# 2403_RAM.net
KiCad netlist of a schematic drawn in Altium Designer
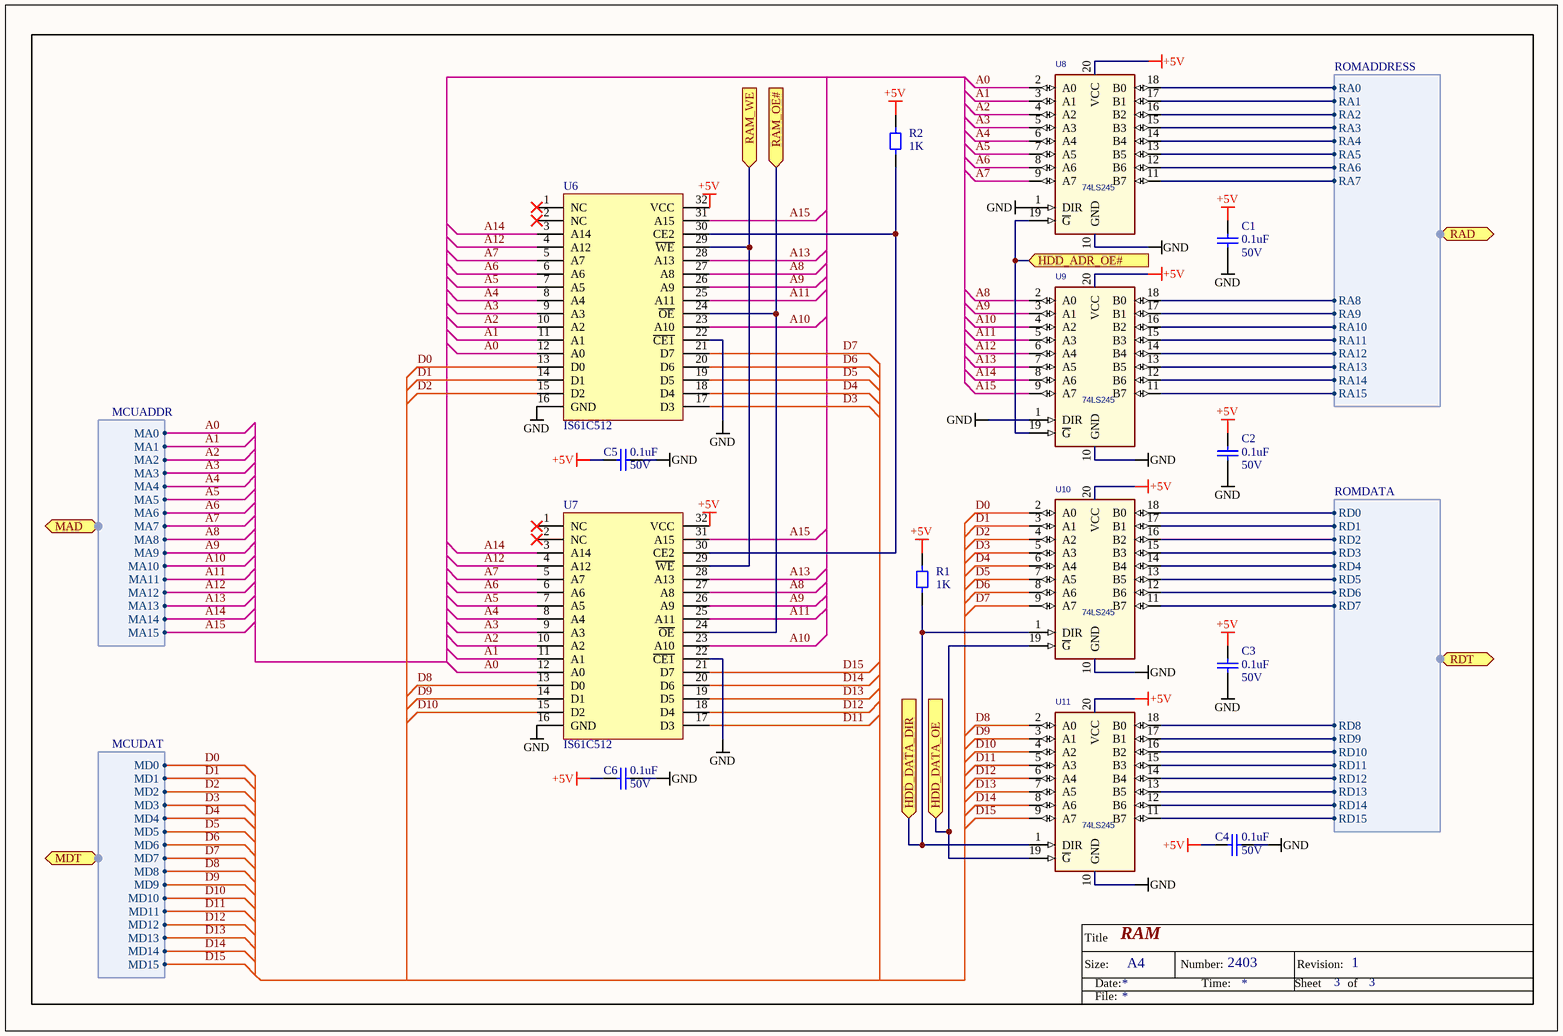
[diagram p0: 2403_RAM.SchDoc]

(export (version "E")
  (design (tool "Eeschema 10.0.6"))
  (components
    (comp (ref "C1")
      (value "0.1uF")
      (footprint "0805_CAPC2013X100N")
      (description "Capacitor SMD")
      (fields (field (name "RATED VOLTAGE") "50V") (field (name "PUBLISHER") "SY"))
      (libsource (lib "Prj24_Library") (part "Cap SMD"))
    )
    (comp (ref "C2")
      (value "0.1uF")
      (footprint "0805_CAPC2013X100N")
      (description "Capacitor SMD")
      (fields (field (name "RATED VOLTAGE") "50V") (field (name "PUBLISHER") "SY"))
      (libsource (lib "Prj24_Library") (part "Cap SMD"))
    )
    (comp (ref "C3")
      (value "0.1uF")
      (footprint "0805_CAPC2013X100N")
      (description "Capacitor SMD")
      (fields (field (name "RATED VOLTAGE") "50V") (field (name "PUBLISHER") "SY"))
      (libsource (lib "Prj24_Library") (part "Cap SMD"))
    )
    (comp (ref "C4")
      (value "0.1uF")
      (footprint "0805_CAPC2013X100N")
      (description "Capacitor SMD")
      (fields (field (name "RATED VOLTAGE") "50V") (field (name "PUBLISHER") "SY"))
      (libsource (lib "Prj24_Library") (part "Cap SMD"))
    )
    (comp (ref "C5")
      (value "0.1uF")
      (footprint "0805_CAPC2013X100N")
      (description "Capacitor SMD")
      (fields (field (name "RATED VOLTAGE") "50V") (field (name "PUBLISHER") "SY"))
      (libsource (lib "Prj24_Library") (part "Cap SMD"))
    )
    (comp (ref "C6")
      (value "0.1uF")
      (footprint "0805_CAPC2013X100N")
      (description "Capacitor SMD")
      (fields (field (name "RATED VOLTAGE") "50V") (field (name "PUBLISHER") "SY"))
      (libsource (lib "Prj24_Library") (part "Cap SMD"))
    )
    (comp (ref "R1")
      (value "1K")
      (footprint "0805_RESC2013X84N")
      (description "SMD Resistor")
      (fields (field (name "TOLERANCE") "5%") (field (name "POWER") "0.1W") (field (name "PUBLISHER") "SY"))
      (libsource (lib "Prj24_Library") (part "Resistor SMD L"))
    )
    (comp (ref "R2")
      (value "1K")
      (footprint "0805_RESC2013X84N")
      (description "SMD Resistor")
      (fields (field (name "TOLERANCE") "5%") (field (name "POWER") "0.1W") (field (name "PUBLISHER") "SY"))
      (libsource (lib "Prj24_Library") (part "Resistor SMD L"))
    )
    (comp (ref "U6")
      (value "IS61C512")
      (footprint "DIP32-300")
      (description "64KB static RAM")
      (fields (field (name "PUBLISHER") "SY"))
      (libsource (lib "Prj24_Library") (part "IS61C512"))
    )
    (comp (ref "U7")
      (value "IS61C512")
      (footprint "DIP32-300")
      (description "64KB static RAM")
      (fields (field (name "PUBLISHER") "SY"))
      (libsource (lib "Prj24_Library") (part "IS61C512"))
    )
    (comp (ref "U8")
      (value "74LS245")
      (footprint "SOIC127P1030X265-20N")
      (description "Bus former")
      (fields (field (name "PUBLISHER") "SY"))
      (libsource (lib "Prj24_Library") (part "74ABT245"))
    )
    (comp (ref "U9")
      (value "74LS245")
      (footprint "SOIC127P1030X265-20N")
      (description "Bus former")
      (fields (field (name "PUBLISHER") "SY"))
      (libsource (lib "Prj24_Library") (part "74ABT245"))
    )
    (comp (ref "U10")
      (value "74LS245")
      (footprint "SOIC127P1030X265-20N")
      (description "Bus former")
      (fields (field (name "PUBLISHER") "SY"))
      (libsource (lib "Prj24_Library") (part "74ABT245"))
    )
    (comp (ref "U11")
      (value "74LS245")
      (footprint "SOIC127P1030X265-20N")
      (description "Bus former")
      (fields (field (name "PUBLISHER") "SY"))
      (libsource (lib "Prj24_Library") (part "74ABT245"))
    )
  )
  (nets
    (net (code "5") (name "+5V") (class "Default")
      (node (ref "C1") (pin "2") (pinfunction "2_2") (pintype "passive"))
      (node (ref "C2") (pin "2") (pinfunction "2_2") (pintype "passive"))
      (node (ref "C3") (pin "2") (pinfunction "2_2") (pintype "passive"))
      (node (ref "C4") (pin "2") (pinfunction "2_2") (pintype "passive"))
      (node (ref "C5") (pin "2") (pinfunction "2_2") (pintype "passive"))
      (node (ref "C6") (pin "2") (pinfunction "2_2") (pintype "passive"))
      (node (ref "R1") (pin "2") (pinfunction "2_2") (pintype "passive"))
      (node (ref "R2") (pin "2") (pinfunction "2_2") (pintype "passive"))
      (node (ref "U10") (pin "20") (pinfunction "VCC_20") (pintype "power_in"))
      (node (ref "U11") (pin "20") (pinfunction "VCC_20") (pintype "power_in"))
      (node (ref "U6") (pin "32") (pinfunction "VCC_32") (pintype "passive"))
      (node (ref "U7") (pin "32") (pinfunction "VCC_32") (pintype "passive"))
      (node (ref "U8") (pin "20") (pinfunction "VCC_20") (pintype "power_in"))
      (node (ref "U9") (pin "20") (pinfunction "VCC_20") (pintype "power_in"))
    )
    (net (code "6") (name "/A0") (class "Default")
      (node (ref "U6") (pin "12") (pinfunction "A0_12") (pintype "passive"))
      (node (ref "U7") (pin "12") (pinfunction "A0_12") (pintype "passive"))
      (node (ref "U8") (pin "2") (pinfunction "A0_2") (pintype "bidirectional"))
    )
    (net (code "7") (name "/A1") (class "Default")
      (node (ref "U6") (pin "11") (pinfunction "A1_11") (pintype "passive"))
      (node (ref "U7") (pin "11") (pinfunction "A1_11") (pintype "passive"))
      (node (ref "U8") (pin "3") (pinfunction "A1_3") (pintype "bidirectional"))
    )
    (net (code "8") (name "/A2") (class "Default")
      (node (ref "U6") (pin "10") (pinfunction "A2_10") (pintype "passive"))
      (node (ref "U7") (pin "10") (pinfunction "A2_10") (pintype "passive"))
      (node (ref "U8") (pin "4") (pinfunction "A2_4") (pintype "bidirectional"))
    )
    (net (code "9") (name "/A3") (class "Default")
      (node (ref "U6") (pin "9") (pinfunction "A3_9") (pintype "passive"))
      (node (ref "U7") (pin "9") (pinfunction "A3_9") (pintype "passive"))
      (node (ref "U8") (pin "5") (pinfunction "A3_5") (pintype "bidirectional"))
    )
    (net (code "10") (name "/A4") (class "Default")
      (node (ref "U6") (pin "8") (pinfunction "A4_8") (pintype "passive"))
      (node (ref "U7") (pin "8") (pinfunction "A4_8") (pintype "passive"))
      (node (ref "U8") (pin "6") (pinfunction "A4_6") (pintype "bidirectional"))
    )
    (net (code "11") (name "/A5") (class "Default")
      (node (ref "U6") (pin "7") (pinfunction "A5_7") (pintype "passive"))
      (node (ref "U7") (pin "7") (pinfunction "A5_7") (pintype "passive"))
      (node (ref "U8") (pin "7") (pinfunction "A5_7") (pintype "bidirectional"))
    )
    (net (code "12") (name "/A6") (class "Default")
      (node (ref "U6") (pin "6") (pinfunction "A6_6") (pintype "passive"))
      (node (ref "U7") (pin "6") (pinfunction "A6_6") (pintype "passive"))
      (node (ref "U8") (pin "8") (pinfunction "A6_8") (pintype "bidirectional"))
    )
    (net (code "13") (name "/A7") (class "Default")
      (node (ref "U6") (pin "5") (pinfunction "A7_5") (pintype "passive"))
      (node (ref "U7") (pin "5") (pinfunction "A7_5") (pintype "passive"))
      (node (ref "U8") (pin "9") (pinfunction "A7_9") (pintype "bidirectional"))
    )
    (net (code "14") (name "/A8") (class "Default")
      (node (ref "U6") (pin "27") (pinfunction "A8_27") (pintype "passive"))
      (node (ref "U7") (pin "27") (pinfunction "A8_27") (pintype "passive"))
      (node (ref "U9") (pin "2") (pinfunction "A0_2") (pintype "bidirectional"))
    )
    (net (code "15") (name "/A9") (class "Default")
      (node (ref "U6") (pin "26") (pinfunction "A9_26") (pintype "passive"))
      (node (ref "U7") (pin "26") (pinfunction "A9_26") (pintype "passive"))
      (node (ref "U9") (pin "3") (pinfunction "A1_3") (pintype "bidirectional"))
    )
    (net (code "16") (name "/A10") (class "Default")
      (node (ref "U6") (pin "23") (pinfunction "A10_23") (pintype "passive"))
      (node (ref "U7") (pin "23") (pinfunction "A10_23") (pintype "passive"))
      (node (ref "U9") (pin "4") (pinfunction "A2_4") (pintype "bidirectional"))
    )
    (net (code "17") (name "/A11") (class "Default")
      (node (ref "U6") (pin "25") (pinfunction "A11_25") (pintype "passive"))
      (node (ref "U7") (pin "25") (pinfunction "A11_25") (pintype "passive"))
      (node (ref "U9") (pin "5") (pinfunction "A3_5") (pintype "bidirectional"))
    )
    (net (code "18") (name "/A12") (class "Default")
      (node (ref "U6") (pin "4") (pinfunction "A12_4") (pintype "passive"))
      (node (ref "U7") (pin "4") (pinfunction "A12_4") (pintype "passive"))
      (node (ref "U9") (pin "6") (pinfunction "A4_6") (pintype "bidirectional"))
    )
    (net (code "19") (name "/A13") (class "Default")
      (node (ref "U6") (pin "28") (pinfunction "A13_28") (pintype "passive"))
      (node (ref "U7") (pin "28") (pinfunction "A13_28") (pintype "passive"))
      (node (ref "U9") (pin "7") (pinfunction "A5_7") (pintype "bidirectional"))
    )
    (net (code "20") (name "/A14") (class "Default")
      (node (ref "U6") (pin "3") (pinfunction "A14_3") (pintype "passive"))
      (node (ref "U7") (pin "3") (pinfunction "A14_3") (pintype "passive"))
      (node (ref "U9") (pin "8") (pinfunction "A6_8") (pintype "bidirectional"))
    )
    (net (code "21") (name "/A15") (class "Default")
      (node (ref "U6") (pin "31") (pinfunction "A15_31") (pintype "passive"))
      (node (ref "U7") (pin "31") (pinfunction "A15_31") (pintype "passive"))
      (node (ref "U9") (pin "9") (pinfunction "A7_9") (pintype "bidirectional"))
    )
    (net (code "22") (name "/D0") (class "Default")
      (node (ref "U10") (pin "2") (pinfunction "A0_2") (pintype "bidirectional"))
      (node (ref "U6") (pin "13") (pinfunction "D0_13") (pintype "passive"))
    )
    (net (code "23") (name "/D1") (class "Default")
      (node (ref "U10") (pin "3") (pinfunction "A1_3") (pintype "bidirectional"))
      (node (ref "U6") (pin "14") (pinfunction "D1_14") (pintype "passive"))
    )
    (net (code "24") (name "/D2") (class "Default")
      (node (ref "U10") (pin "4") (pinfunction "A2_4") (pintype "bidirectional"))
      (node (ref "U6") (pin "15") (pinfunction "D2_15") (pintype "passive"))
    )
    (net (code "25") (name "/D3") (class "Default")
      (node (ref "U10") (pin "5") (pinfunction "A3_5") (pintype "bidirectional"))
      (node (ref "U6") (pin "17") (pinfunction "D3_17") (pintype "passive"))
    )
    (net (code "26") (name "/D4") (class "Default")
      (node (ref "U10") (pin "6") (pinfunction "A4_6") (pintype "bidirectional"))
      (node (ref "U6") (pin "18") (pinfunction "D4_18") (pintype "passive"))
    )
    (net (code "27") (name "/D5") (class "Default")
      (node (ref "U10") (pin "7") (pinfunction "A5_7") (pintype "bidirectional"))
      (node (ref "U6") (pin "19") (pinfunction "D5_19") (pintype "passive"))
    )
    (net (code "28") (name "/D6") (class "Default")
      (node (ref "U10") (pin "8") (pinfunction "A6_8") (pintype "bidirectional"))
      (node (ref "U6") (pin "20") (pinfunction "D6_20") (pintype "passive"))
    )
    (net (code "29") (name "/D7") (class "Default")
      (node (ref "U10") (pin "9") (pinfunction "A7_9") (pintype "bidirectional"))
      (node (ref "U6") (pin "21") (pinfunction "D7_21") (pintype "passive"))
    )
    (net (code "30") (name "/D8") (class "Default")
      (node (ref "U11") (pin "2") (pinfunction "A0_2") (pintype "bidirectional"))
      (node (ref "U7") (pin "13") (pinfunction "D0_13") (pintype "passive"))
    )
    (net (code "31") (name "/D9") (class "Default")
      (node (ref "U11") (pin "3") (pinfunction "A1_3") (pintype "bidirectional"))
      (node (ref "U7") (pin "14") (pinfunction "D1_14") (pintype "passive"))
    )
    (net (code "32") (name "/D10") (class "Default")
      (node (ref "U11") (pin "4") (pinfunction "A2_4") (pintype "bidirectional"))
      (node (ref "U7") (pin "15") (pinfunction "D2_15") (pintype "passive"))
    )
    (net (code "33") (name "/D11") (class "Default")
      (node (ref "U11") (pin "5") (pinfunction "A3_5") (pintype "bidirectional"))
      (node (ref "U7") (pin "17") (pinfunction "D3_17") (pintype "passive"))
    )
    (net (code "34") (name "/D12") (class "Default")
      (node (ref "U11") (pin "6") (pinfunction "A4_6") (pintype "bidirectional"))
      (node (ref "U7") (pin "18") (pinfunction "D4_18") (pintype "passive"))
    )
    (net (code "35") (name "/D13") (class "Default")
      (node (ref "U11") (pin "7") (pinfunction "A5_7") (pintype "bidirectional"))
      (node (ref "U7") (pin "19") (pinfunction "D5_19") (pintype "passive"))
    )
    (net (code "36") (name "/D14") (class "Default")
      (node (ref "U11") (pin "8") (pinfunction "A6_8") (pintype "bidirectional"))
      (node (ref "U7") (pin "20") (pinfunction "D6_20") (pintype "passive"))
    )
    (net (code "37") (name "/D15") (class "Default")
      (node (ref "U11") (pin "9") (pinfunction "A7_9") (pintype "bidirectional"))
      (node (ref "U7") (pin "21") (pinfunction "D7_21") (pintype "passive"))
    )
    (net (code "38") (name "/HDD_ADR_OE#") (class "Default")
      (node (ref "U8") (pin "19") (pinfunction "~{G}_19") (pintype "input"))
      (node (ref "U9") (pin "19") (pinfunction "~{G}_19") (pintype "input"))
    )
    (net (code "39") (name "/HDD_DATA_DIR") (class "Default")
      (node (ref "R1") (pin "1") (pinfunction "1_1") (pintype "passive"))
      (node (ref "U10") (pin "1") (pinfunction "DIR_1") (pintype "input"))
      (node (ref "U11") (pin "1") (pinfunction "DIR_1") (pintype "input"))
    )
    (net (code "40") (name "/HDD_DATA_OE") (class "Default")
      (node (ref "U10") (pin "19") (pinfunction "~{G}_19") (pintype "input"))
      (node (ref "U11") (pin "19") (pinfunction "~{G}_19") (pintype "input"))
    )
    (net (code "41") (name "/RA0") (class "Default")
      (node (ref "U8") (pin "18") (pinfunction "B0_18") (pintype "bidirectional"))
    )
    (net (code "42") (name "/RA1") (class "Default")
      (node (ref "U8") (pin "17") (pinfunction "B1_17") (pintype "bidirectional"))
    )
    (net (code "43") (name "/RA2") (class "Default")
      (node (ref "U8") (pin "16") (pinfunction "B2_16") (pintype "bidirectional"))
    )
    (net (code "44") (name "/RA3") (class "Default")
      (node (ref "U8") (pin "15") (pinfunction "B3_15") (pintype "bidirectional"))
    )
    (net (code "45") (name "/RA4") (class "Default")
      (node (ref "U8") (pin "14") (pinfunction "B4_14") (pintype "bidirectional"))
    )
    (net (code "46") (name "/RA5") (class "Default")
      (node (ref "U8") (pin "13") (pinfunction "B5_13") (pintype "bidirectional"))
    )
    (net (code "47") (name "/RA6") (class "Default")
      (node (ref "U8") (pin "12") (pinfunction "B6_12") (pintype "bidirectional"))
    )
    (net (code "48") (name "/RA7") (class "Default")
      (node (ref "U8") (pin "11") (pinfunction "B7_11") (pintype "bidirectional"))
    )
    (net (code "49") (name "/RA8") (class "Default")
      (node (ref "U9") (pin "18") (pinfunction "B0_18") (pintype "bidirectional"))
    )
    (net (code "50") (name "/RA9") (class "Default")
      (node (ref "U9") (pin "17") (pinfunction "B1_17") (pintype "bidirectional"))
    )
    (net (code "51") (name "/RA10") (class "Default")
      (node (ref "U9") (pin "16") (pinfunction "B2_16") (pintype "bidirectional"))
    )
    (net (code "52") (name "/RA11") (class "Default")
      (node (ref "U9") (pin "15") (pinfunction "B3_15") (pintype "bidirectional"))
    )
    (net (code "53") (name "/RA12") (class "Default")
      (node (ref "U9") (pin "14") (pinfunction "B4_14") (pintype "bidirectional"))
    )
    (net (code "54") (name "/RA13") (class "Default")
      (node (ref "U9") (pin "13") (pinfunction "B5_13") (pintype "bidirectional"))
    )
    (net (code "55") (name "/RA14") (class "Default")
      (node (ref "U9") (pin "12") (pinfunction "B6_12") (pintype "bidirectional"))
    )
    (net (code "56") (name "/RA15") (class "Default")
      (node (ref "U9") (pin "11") (pinfunction "B7_11") (pintype "bidirectional"))
    )
    (net (code "57") (name "/RAM_OE#") (class "Default")
      (node (ref "U6") (pin "24") (pinfunction "~{OE}_24") (pintype "passive"))
      (node (ref "U7") (pin "24") (pinfunction "~{OE}_24") (pintype "passive"))
    )
    (net (code "58") (name "/RAM_WE") (class "Default")
      (node (ref "U6") (pin "29") (pinfunction "~{WE}_29") (pintype "passive"))
      (node (ref "U7") (pin "29") (pinfunction "~{WE}_29") (pintype "passive"))
    )
    (net (code "59") (name "/RD0") (class "Default")
      (node (ref "U10") (pin "18") (pinfunction "B0_18") (pintype "bidirectional"))
    )
    (net (code "60") (name "/RD1") (class "Default")
      (node (ref "U10") (pin "17") (pinfunction "B1_17") (pintype "bidirectional"))
    )
    (net (code "61") (name "/RD2") (class "Default")
      (node (ref "U10") (pin "16") (pinfunction "B2_16") (pintype "bidirectional"))
    )
    (net (code "62") (name "/RD3") (class "Default")
      (node (ref "U10") (pin "15") (pinfunction "B3_15") (pintype "bidirectional"))
    )
    (net (code "63") (name "/RD4") (class "Default")
      (node (ref "U10") (pin "14") (pinfunction "B4_14") (pintype "bidirectional"))
    )
    (net (code "64") (name "/RD5") (class "Default")
      (node (ref "U10") (pin "13") (pinfunction "B5_13") (pintype "bidirectional"))
    )
    (net (code "65") (name "/RD6") (class "Default")
      (node (ref "U10") (pin "12") (pinfunction "B6_12") (pintype "bidirectional"))
    )
    (net (code "66") (name "/RD7") (class "Default")
      (node (ref "U10") (pin "11") (pinfunction "B7_11") (pintype "bidirectional"))
    )
    (net (code "67") (name "/RD8") (class "Default")
      (node (ref "U11") (pin "18") (pinfunction "B0_18") (pintype "bidirectional"))
    )
    (net (code "68") (name "/RD9") (class "Default")
      (node (ref "U11") (pin "17") (pinfunction "B1_17") (pintype "bidirectional"))
    )
    (net (code "69") (name "/RD10") (class "Default")
      (node (ref "U11") (pin "16") (pinfunction "B2_16") (pintype "bidirectional"))
    )
    (net (code "70") (name "/RD11") (class "Default")
      (node (ref "U11") (pin "15") (pinfunction "B3_15") (pintype "bidirectional"))
    )
    (net (code "71") (name "/RD12") (class "Default")
      (node (ref "U11") (pin "14") (pinfunction "B4_14") (pintype "bidirectional"))
    )
    (net (code "72") (name "/RD13") (class "Default")
      (node (ref "U11") (pin "13") (pinfunction "B5_13") (pintype "bidirectional"))
    )
    (net (code "73") (name "/RD14") (class "Default")
      (node (ref "U11") (pin "12") (pinfunction "B6_12") (pintype "bidirectional"))
    )
    (net (code "74") (name "/RD15") (class "Default")
      (node (ref "U11") (pin "11") (pinfunction "B7_11") (pintype "bidirectional"))
    )
    (net (code "79") (name "GND") (class "Default")
      (node (ref "C1") (pin "1") (pinfunction "1_1") (pintype "passive"))
      (node (ref "C2") (pin "1") (pinfunction "1_1") (pintype "passive"))
      (node (ref "C3") (pin "1") (pinfunction "1_1") (pintype "passive"))
      (node (ref "C4") (pin "1") (pinfunction "1_1") (pintype "passive"))
      (node (ref "C5") (pin "1") (pinfunction "1_1") (pintype "passive"))
      (node (ref "C6") (pin "1") (pinfunction "1_1") (pintype "passive"))
      (node (ref "U10") (pin "10") (pinfunction "GND_10") (pintype "power_in"))
      (node (ref "U11") (pin "10") (pinfunction "GND_10") (pintype "power_in"))
      (node (ref "U6") (pin "16") (pinfunction "GND_16") (pintype "passive"))
      (node (ref "U6") (pin "22") (pinfunction "~{CE1}_22") (pintype "passive"))
      (node (ref "U7") (pin "16") (pinfunction "GND_16") (pintype "passive"))
      (node (ref "U7") (pin "22") (pinfunction "~{CE1}_22") (pintype "passive"))
      (node (ref "U8") (pin "1") (pinfunction "DIR_1") (pintype "input"))
      (node (ref "U8") (pin "10") (pinfunction "GND_10") (pintype "power_in"))
      (node (ref "U9") (pin "1") (pinfunction "DIR_1") (pintype "input"))
      (node (ref "U9") (pin "10") (pinfunction "GND_10") (pintype "power_in"))
    )
    (net (code "80") (name "Net-(U6-CE2)") (class "Default")
      (node (ref "R2") (pin "1") (pinfunction "1_1") (pintype "passive"))
      (node (ref "U6") (pin "30") (pinfunction "CE2_30") (pintype "passive"))
      (node (ref "U7") (pin "30") (pinfunction "CE2_30") (pintype "passive"))
    )
    (net (code "81") (name "unconnected-(U6-NC-Pad1)") (class "Default")
      (node (ref "U6") (pin "1") (pinfunction "NC_1") (pintype "passive+no_connect"))
    )
    (net (code "82") (name "unconnected-(U6-NC-Pad2)") (class "Default")
      (node (ref "U6") (pin "2") (pinfunction "NC_2") (pintype "passive+no_connect"))
    )
    (net (code "83") (name "unconnected-(U7-NC-Pad1)") (class "Default")
      (node (ref "U7") (pin "1") (pinfunction "NC_1") (pintype "passive+no_connect"))
    )
    (net (code "84") (name "unconnected-(U7-NC-Pad2)") (class "Default")
      (node (ref "U7") (pin "2") (pinfunction "NC_2") (pintype "passive+no_connect"))
    )
  )
)
